# Voltage_Regulator.net
KiCad netlist of a schematic drawn in Altium Designer
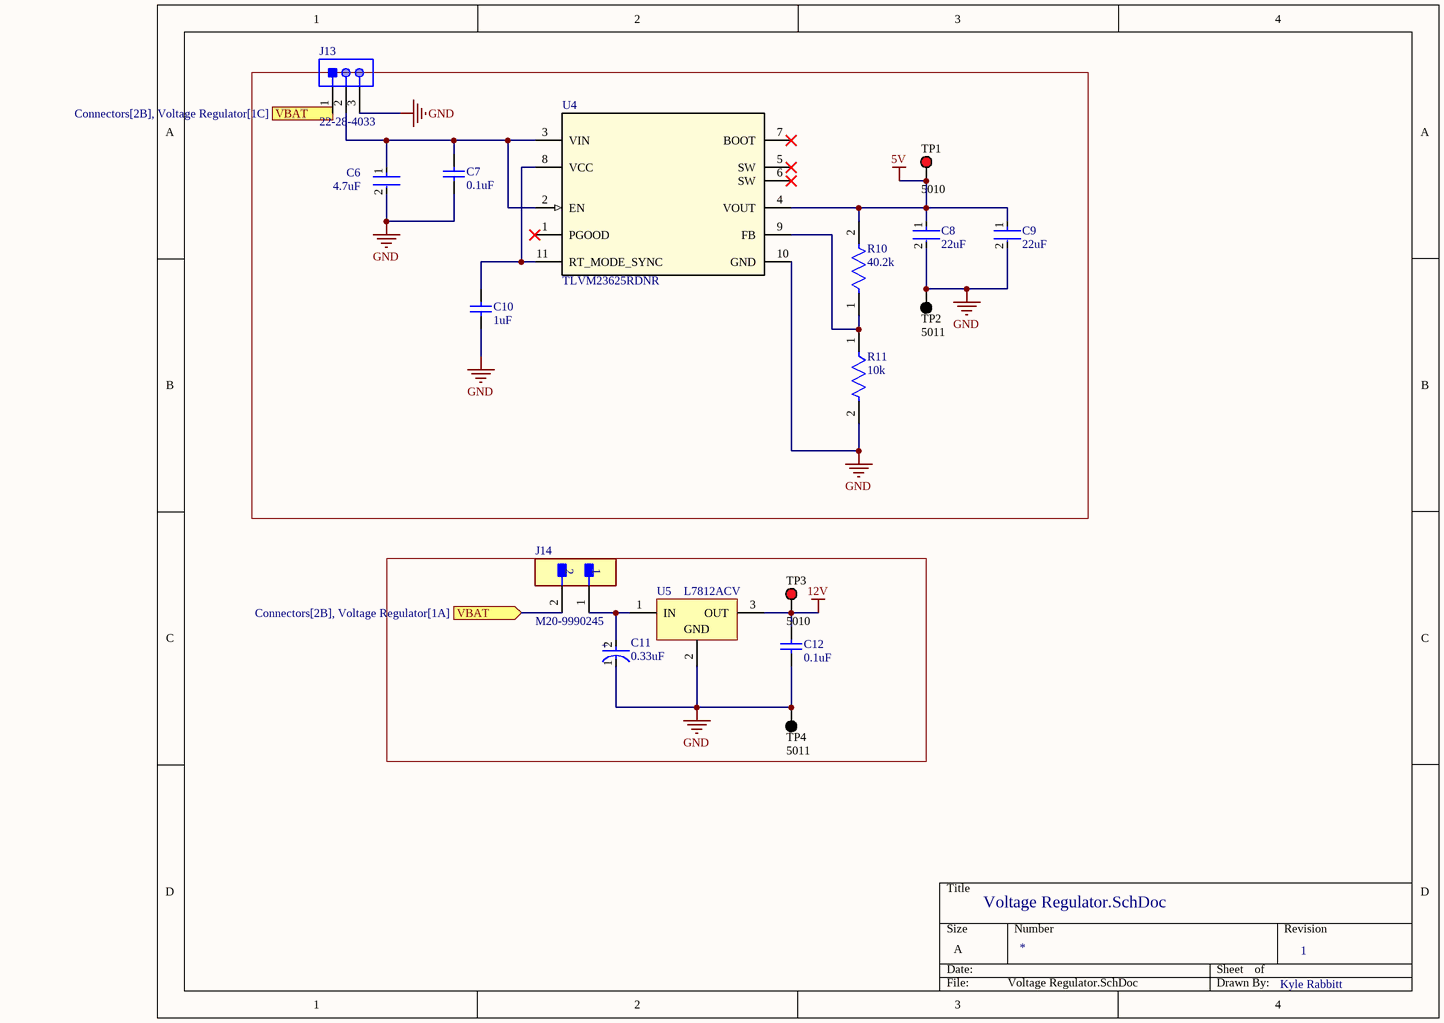
[diagram p0: Voltage Regulator.SchDoc]

(export (version "E")
  (design (tool "Eeschema 10.0.6"))
  (components
    (comp (ref "C6")
      (value "4.7uF")
      (footprint "FP-C1210X475K5RACTU-MFG")
      (description "CAP CER 4.7UF 50V X7R 1210")
      (fields (field (name "TOLERANCE") "10%") (field (name "VOLTAGE") "50V"))
      (libsource (lib "Altium Content Vault") (part "02cd4be3c70576c341d710602a673aa"))
    )
    (comp (ref "C7")
      (value "0.1uF")
      (footprint "CAPC1608X90X35ML10T15")
      (description "Chip Capacitor, 0.1 uF, +/- 10%, 50 V, -55 to 125 degC, 0603 (1608 Metric), RoHS, Tape and Reel")
      (fields (field (name "TOLERANCE") "10%") (field (name "VOLTAGE") "50V"))
      (libsource (lib "Altium Content Vault") (part "CAP-NP-2"))
    )
    (comp (ref "C8")
      (value "22uF")
      (footprint "FP-1210-L_3_3_0_4-W_2_5_0-MFG")
      (description "General Purpose Ceramic Capacitor, 1210, 22uF, 10%, X5R, 15%, 16V")
      (fields (field (name "TOLERANCE") "10%") (field (name "VOLTAGE") "16V"))
      (libsource (lib "Altium Content Vault") (part "b4654b650e69147ec39a6b967a45e02"))
    )
    (comp (ref "C9")
      (value "22uF")
      (footprint "FP-1210-L_3_3_0_4-W_2_5_0-MFG")
      (description "General Purpose Ceramic Capacitor, 1210, 22uF, 10%, X5R, 15%, 16V")
      (fields (field (name "TOLERANCE") "10%") (field (name "VOLTAGE") "16V"))
      (libsource (lib "Altium Content Vault") (part "b4654b650e69147ec39a6b967a45e02"))
    )
    (comp (ref "C10")
      (value "1uF")
      (footprint "CAPC2013X145X50LL20T25")
      (fields (field (name "MANUFACTURER") "Kemet") (field (name "PART NUMBER") "C0805C105K4PACTU"))
      (libsource (lib "Altium Content Vault") (part "CAP"))
    )
    (comp (ref "C11")
      (value "0.33uF")
      (footprint "FP-TAJS-MFG")
      (description "330nF 35V  ±10% 15Ω 1206  SMD Tantalum Capacitor")
      (fields (field (name "TOLERANCE") "10%"))
      (libsource (lib "Altium Content Vault") (part "a00bbbee19879c290e62620ae7e47b1"))
    )
    (comp (ref "C12")
      (value "0.1uF")
      (footprint "CAPC1608X90X35ML10T15")
      (description "Chip Capacitor, 0.1 uF, +/- 10%, 50 V, -55 to 125 degC, 0603 (1608 Metric), RoHS, Tape and Reel")
      (fields (field (name "TOLERANCE") "10%") (field (name "VOLTAGE") "50V"))
      (libsource (lib "Altium Content Vault") (part "CAP-NP-2"))
    )
    (comp (ref "J13")
      (value "22-28-4033")
      (footprint "MOLX-22-28-4033_V")
      (description "Male Header, Pitch 2.54 mm, 1 x 3 Position, Height 8.38 mm, Tail Length 3.18 mm, RoHS, Bulk")
      (fields (field (name "MANUFACTURER") "Molex"))
      (libsource (lib "Altium Content Vault") (part "CN-1P-M-R3"))
    )
    (comp (ref "J14")
      (value "M20-9990245")
      (footprint "FP-M20-9990245-MFG")
      (description "CONN HEADER VERT 2POS 2.54MM")
      (fields (field (name "VOLTAGE") "50V"))
      (libsource (lib "Altium Content Vault") (part "3bc925449376181038e59eaffc5286c"))
    )
    (comp (ref "R10")
      (value "40.2k")
      (footprint "FP-CRCW0603-e3-IPC_B")
      (description "RES Thick Film, 40.2kΩ, 1%, 0.1W, 100ppm/°C, 0603")
      (fields (field (name "TOLERANCE") "1%"))
      (libsource (lib "Altium Content Vault") (part "1029c3af85768c4190bb7ad29bc67b5"))
    )
    (comp (ref "R11")
      (value "10k")
      (footprint "FP-MCT0603-IPC_C")
      (description "RES SMD 100 OHM 1% 1/8W 0603")
      (fields (field (name "TOLERANCE") "1%"))
      (libsource (lib "Altium Content Vault") (part "1029c3af85768c4190bb7ad29bc67b5"))
    )
    (comp (ref "TP1")
      (value "5010")
      (footprint "KSTN-5010_V")
      (description "Test Point, Red, Through Hole, RoHS, Bulk")
      (fields (field (name "MANUFACTURER") "Keystone"))
      (libsource (lib "Altium Content Vault") (part "TESTPOINT_RED"))
    )
    (comp (ref "TP2")
      (value "5011")
      (footprint "KSTN-5011_V")
      (description "Test Point, Black, Through Hole, RoHS, Bulk")
      (fields (field (name "MANUFACTURER") "Keystone"))
      (libsource (lib "Altium Content Vault") (part "TESTPOINT_BLACK"))
    )
    (comp (ref "TP3")
      (value "5010")
      (footprint "KSTN-5010_V")
      (description "Test Point, Red, Through Hole, RoHS, Bulk")
      (fields (field (name "MANUFACTURER") "Keystone"))
      (libsource (lib "Altium Content Vault") (part "TESTPOINT_RED"))
    )
    (comp (ref "TP4")
      (value "5011")
      (footprint "KSTN-5011_V")
      (description "Test Point, Black, Through Hole, RoHS, Bulk")
      (fields (field (name "MANUFACTURER") "Keystone"))
      (libsource (lib "Altium Content Vault") (part "TESTPOINT_BLACK"))
    )
    (comp (ref "U4")
      (value "TLVM23625RDNR")
      (footprint "TLVM23625RDNR:RDN0011A-MFG")
      (description "No Description Available")
      (libsource (lib "TLVM23625RDNR") (part "TLVM23625RDNR"))
    )
    (comp (ref "U5")
      (value "L7812ACV")
      (footprint "TO220")
      (description "Positive Voltage Regulator, 12V, 3-Pin TO-220")
      (libsource (lib "Altium Content Vault") (part "PM-REG-L4940-SIL3"))
    )
  )
  (nets
    (net (code "1") (name "/VBAT") (class "Default")
      (node (ref "J13") (pin "1") (pinfunction "1_1") (pintype "passive"))
      (node (ref "J14") (pin "2") (pinfunction "2_2") (pintype "passive"))
    )
    (net (code "2") (name "5V") (class "Default")
      (node (ref "C8") (pin "1") (pinfunction "1_1") (pintype "passive"))
      (node (ref "C9") (pin "1") (pinfunction "1_1") (pintype "passive"))
      (node (ref "R10") (pin "2") (pinfunction "2_2") (pintype "passive"))
      (node (ref "TP1") (pin "1") (pinfunction "1_1") (pintype "passive"))
      (node (ref "U4") (pin "4") (pinfunction "VOUT_4") (pintype "power_in"))
    )
    (net (code "3") (name "12V") (class "Default")
      (node (ref "C12") (pin "2") (pinfunction "2_2") (pintype "passive"))
      (node (ref "TP3") (pin "1") (pinfunction "1_1") (pintype "passive"))
      (node (ref "U5") (pin "3") (pinfunction "OUT_3") (pintype "power_in"))
    )
    (net (code "4") (name "GND") (class "Default")
      (node (ref "C10") (pin "1") (pinfunction "1_1") (pintype "passive"))
      (node (ref "C11") (pin "1") (pinfunction "C_1") (pintype "passive"))
      (node (ref "C12") (pin "1") (pinfunction "1_1") (pintype "passive"))
      (node (ref "C6") (pin "2") (pinfunction "2_2") (pintype "passive"))
      (node (ref "C7") (pin "1") (pinfunction "1_1") (pintype "passive"))
      (node (ref "C8") (pin "2") (pinfunction "2_2") (pintype "passive"))
      (node (ref "C9") (pin "2") (pinfunction "2_2") (pintype "passive"))
      (node (ref "J13") (pin "3") (pinfunction "3_3") (pintype "passive"))
      (node (ref "R11") (pin "2") (pinfunction "2_2") (pintype "passive"))
      (node (ref "TP2") (pin "1") (pinfunction "1_1") (pintype "passive"))
      (node (ref "TP4") (pin "1") (pinfunction "1_1") (pintype "passive"))
      (node (ref "U4") (pin "10") (pinfunction "GND_10") (pintype "power_in"))
      (node (ref "U5") (pin "2") (pinfunction "GND_2") (pintype "power_in"))
    )
    (net (code "5") (name "Net-(C11-A)") (class "Default")
      (node (ref "C11") (pin "2") (pinfunction "A_2") (pintype "passive"))
      (node (ref "J14") (pin "1") (pinfunction "1_1") (pintype "passive"))
      (node (ref "U5") (pin "1") (pinfunction "IN_1") (pintype "power_in"))
    )
    (net (code "6") (name "Net-(U4-EN)") (class "Default")
      (node (ref "C6") (pin "1") (pinfunction "1_1") (pintype "passive"))
      (node (ref "C7") (pin "2") (pinfunction "2_2") (pintype "passive"))
      (node (ref "J13") (pin "2") (pinfunction "2_2") (pintype "passive"))
      (node (ref "U4") (pin "2") (pinfunction "EN_2") (pintype "input"))
      (node (ref "U4") (pin "3") (pinfunction "VIN_3") (pintype "power_in"))
    )
    (net (code "7") (name "Net-(U4-FB)") (class "Default")
      (node (ref "R10") (pin "1") (pinfunction "1_1") (pintype "passive"))
      (node (ref "R11") (pin "1") (pinfunction "1_1") (pintype "passive"))
      (node (ref "U4") (pin "9") (pinfunction "FB_9") (pintype "passive"))
    )
    (net (code "8") (name "Net-(U4-RT_MODE_SYNC)") (class "Default")
      (node (ref "C10") (pin "2") (pinfunction "2_2") (pintype "passive"))
      (node (ref "U4") (pin "11") (pinfunction "RT_MODE_SYNC_11") (pintype "passive"))
      (node (ref "U4") (pin "8") (pinfunction "VCC_8") (pintype "passive"))
    )
    (net (code "9") (name "unconnected-(U4-BOOT-Pad7)") (class "Default")
      (node (ref "U4") (pin "7") (pinfunction "BOOT_7") (pintype "passive+no_connect"))
    )
    (net (code "10") (name "unconnected-(U4-PGOOD-Pad1)") (class "Default")
      (node (ref "U4") (pin "1") (pinfunction "PGOOD_1") (pintype "open_collector+no_connect"))
    )
    (net (code "11") (name "unconnected-(U4-SW-Pad5)") (class "Default")
      (node (ref "U4") (pin "5") (pinfunction "SW_5") (pintype "passive+no_connect"))
    )
    (net (code "12") (name "unconnected-(U4-SW-Pad6)") (class "Default")
      (node (ref "U4") (pin "6") (pinfunction "SW_6") (pintype "passive+no_connect"))
    )
  )
)
